# masterboard.net
KiCad netlist of a schematic drawn in EAGLE
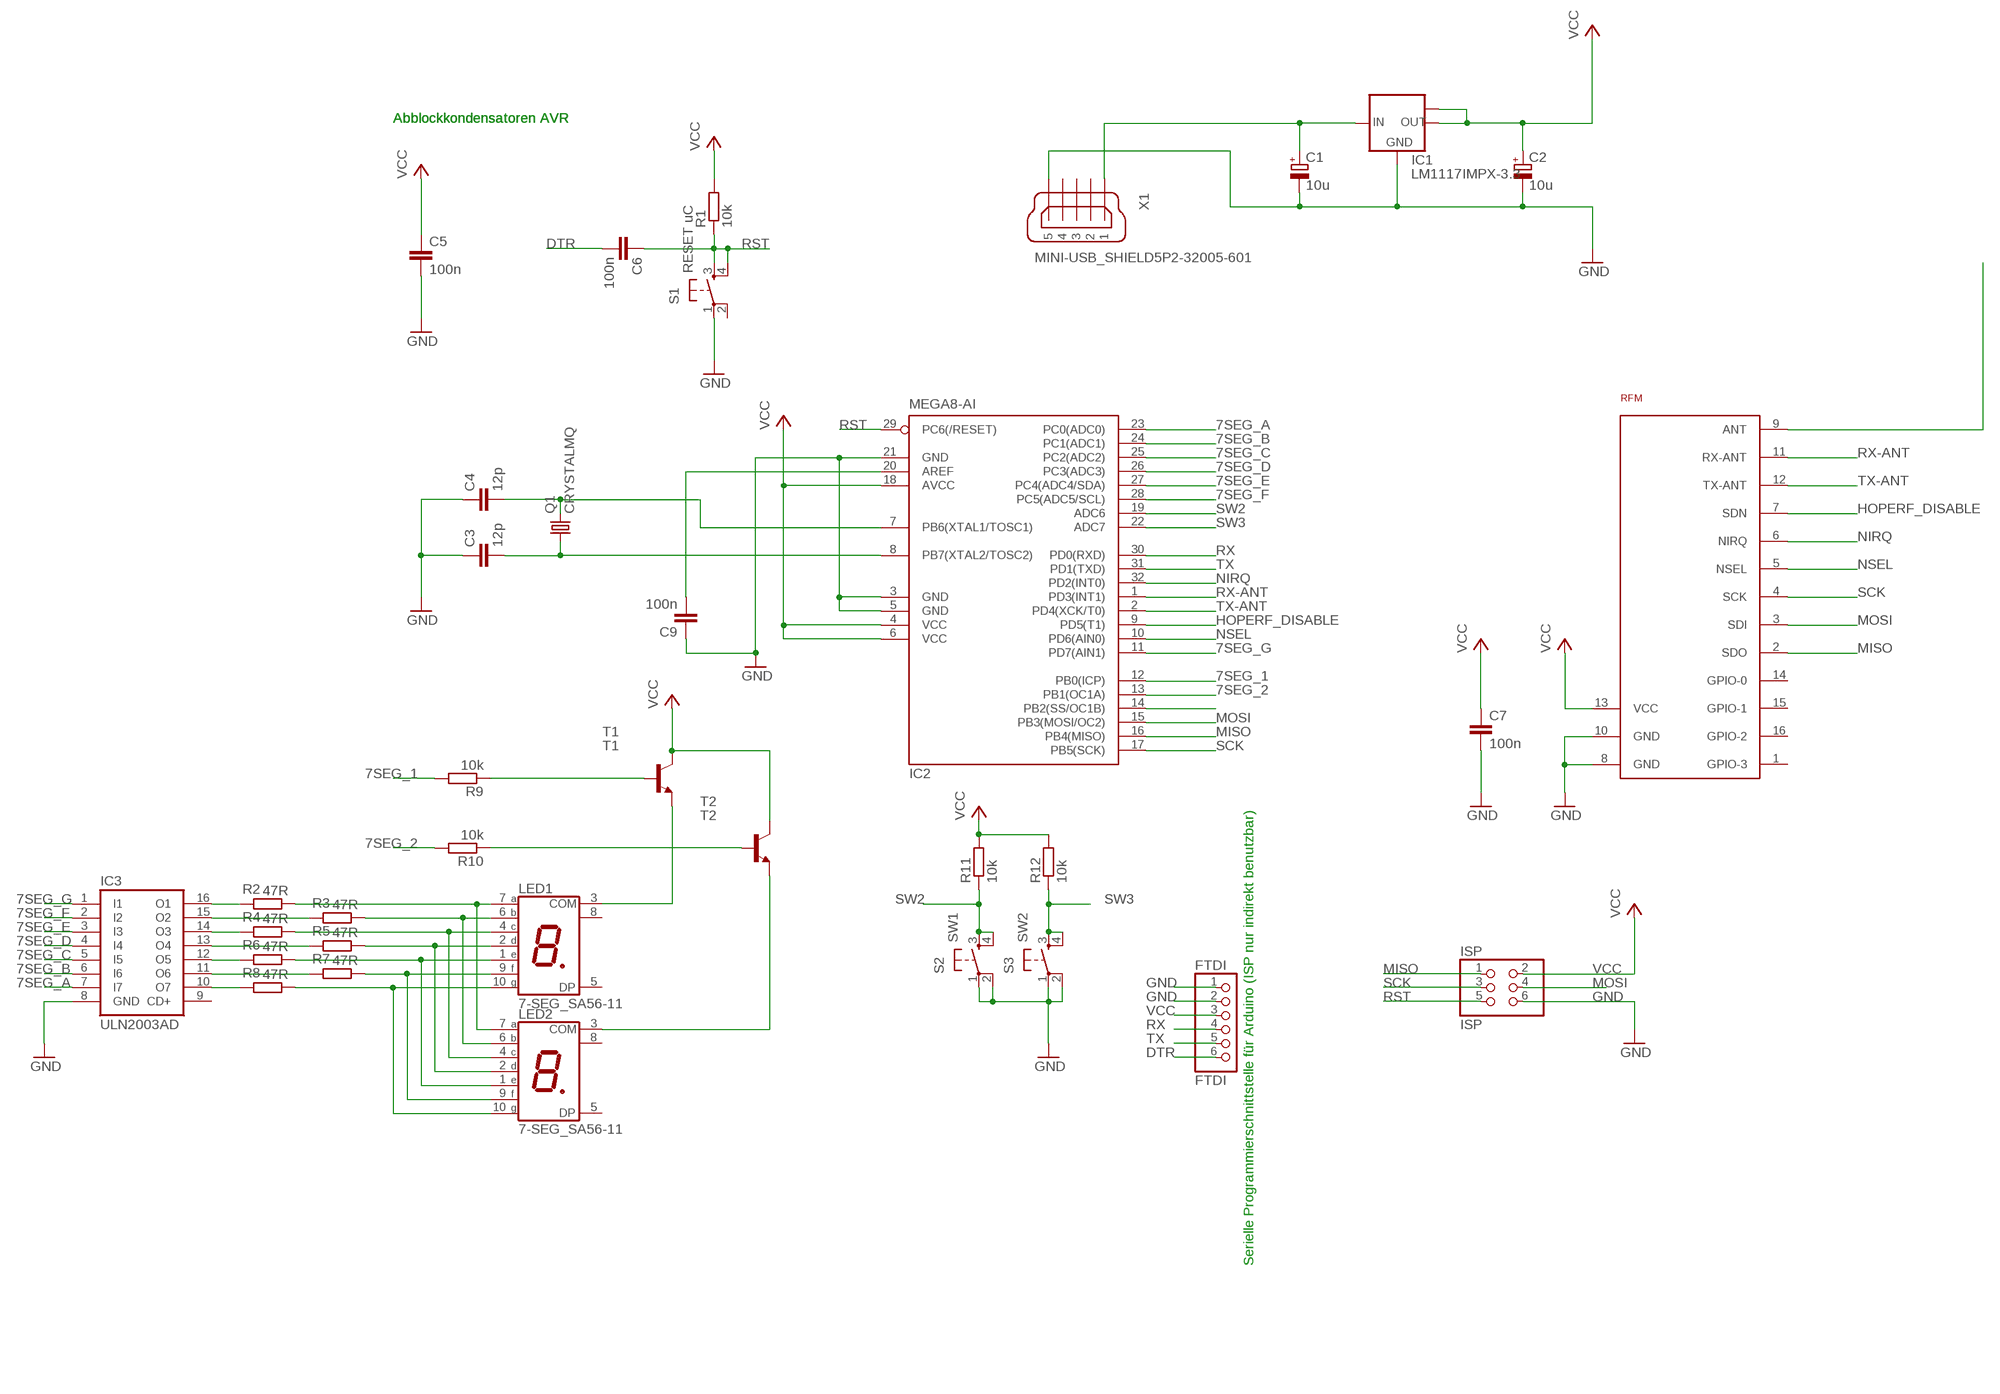
[diagram p0: schematic, sheet 1]

(export (version "E")
  (design (tool "Eeschema 10.0.6"))
  (components
    (comp (ref "C1")
      (value "10u")
      (footprint "eagle-import:CT6032")
      (libsource (lib "eagle-import") (part "CPOL-EUCT6032"))
    )
    (comp (ref "C2")
      (value "10u")
      (footprint "eagle-import:CT6032")
      (libsource (lib "eagle-import") (part "CPOL-EUCT6032"))
    )
    (comp (ref "C3")
      (value "12p")
      (footprint "eagle-import:C0603")
      (libsource (lib "eagle-import") (part "C-EUC0603"))
    )
    (comp (ref "C4")
      (value "12p")
      (footprint "eagle-import:C0603")
      (libsource (lib "eagle-import") (part "C-EUC0603"))
    )
    (comp (ref "C5")
      (value "100n")
      (footprint "eagle-import:C0603")
      (libsource (lib "eagle-import") (part "C-EUC0603"))
    )
    (comp (ref "C6")
      (value "100n")
      (footprint "eagle-import:C0603")
      (libsource (lib "eagle-import") (part "C-EUC0603"))
    )
    (comp (ref "C7")
      (value "100n")
      (footprint "eagle-import:C0603")
      (libsource (lib "eagle-import") (part "C-EUC0603"))
    )
    (comp (ref "C9")
      (value "100n")
      (footprint "eagle-import:C0603")
      (libsource (lib "eagle-import") (part "C-EUC0603"))
    )
    (comp (ref "FTDI")
      (value "FTDI")
      (footprint "eagle-import:1X06_90")
      (libsource (lib "eagle-import") (part "PINHD-1X6/90"))
    )
    (comp (ref "IC1")
      (value "LM1117IMPX-3.3")
      (footprint "eagle-import:SOT223")
      (libsource (lib "eagle-import") (part "LM1117IMPX-3.3"))
    )
    (comp (ref "IC2")
      (value "MEGA8-AI")
      (footprint "eagle-import:TQFP32-08")
      (fields (field (name "MPN") "ATMEGA8-16AU"))
      (libsource (lib "eagle-import") (part "MEGA8-AI"))
    )
    (comp (ref "IC3")
      (value "ULN2003AD")
      (footprint "eagle-import:SO16")
      (libsource (lib "eagle-import") (part "ULN2003AD"))
    )
    (comp (ref "ISP")
      (value "ISP")
      (footprint "eagle-import:2X03")
      (libsource (lib "eagle-import") (part "PINHD-2X3"))
    )
    (comp (ref "LED1")
      (value "7-SEG_SA56-11")
      (footprint "eagle-import:SA56-11")
      (libsource (lib "eagle-import") (part "7-SEG_SA56-11"))
    )
    (comp (ref "LED2")
      (value "7-SEG_SA56-11")
      (footprint "eagle-import:SA56-11")
      (libsource (lib "eagle-import") (part "7-SEG_SA56-11"))
    )
    (comp (ref "Q1")
      (value "CRYSTALMQ")
      (footprint "eagle-import:MQ")
      (libsource (lib "eagle-import") (part "CRYSTALMQ"))
    )
    (comp (ref "R1")
      (value "10k")
      (footprint "eagle-import:R0805")
      (libsource (lib "eagle-import") (part "R-EU_R0805"))
    )
    (comp (ref "R2")
      (value "47R")
      (footprint "eagle-import:R0805")
      (libsource (lib "eagle-import") (part "R-EU_R0805"))
    )
    (comp (ref "R3")
      (value "47R")
      (footprint "eagle-import:R0805")
      (libsource (lib "eagle-import") (part "R-EU_R0805"))
    )
    (comp (ref "R4")
      (value "47R")
      (footprint "eagle-import:R0805")
      (libsource (lib "eagle-import") (part "R-EU_R0805"))
    )
    (comp (ref "R5")
      (value "47R")
      (footprint "eagle-import:R0805")
      (libsource (lib "eagle-import") (part "R-EU_R0805"))
    )
    (comp (ref "R6")
      (value "47R")
      (footprint "eagle-import:R0805")
      (libsource (lib "eagle-import") (part "R-EU_R0805"))
    )
    (comp (ref "R7")
      (value "47R")
      (footprint "eagle-import:R0805")
      (libsource (lib "eagle-import") (part "R-EU_R0805"))
    )
    (comp (ref "R8")
      (value "47R")
      (footprint "eagle-import:R0805")
      (libsource (lib "eagle-import") (part "R-EU_R0805"))
    )
    (comp (ref "R9")
      (value "10k")
      (footprint "eagle-import:R0805")
      (libsource (lib "eagle-import") (part "R-EU_R0805"))
    )
    (comp (ref "R10")
      (value "10k")
      (footprint "eagle-import:R0805")
      (libsource (lib "eagle-import") (part "R-EU_R0805"))
    )
    (comp (ref "R11")
      (value "10k")
      (footprint "eagle-import:R0805")
      (libsource (lib "eagle-import") (part "R-EU_R0805"))
    )
    (comp (ref "R12")
      (value "10k")
      (footprint "eagle-import:R0805")
      (libsource (lib "eagle-import") (part "R-EU_R0805"))
    )
    (comp (ref "RFM")
      (value "HOPERF-DB")
      (footprint "eagle-import:HOPERF-DB")
      (libsource (lib "eagle-import") (part "HOPERF-DB"))
    )
    (comp (ref "S1")
      (value "RESET uC")
      (footprint "eagle-import:RAFI")
      (libsource (lib "eagle-import") (part "10-XXB3FRAFI"))
    )
    (comp (ref "S2")
      (value "SW1")
      (footprint "eagle-import:RAFI")
      (libsource (lib "eagle-import") (part "10-XXB3FRAFI"))
    )
    (comp (ref "S3")
      (value "SW2")
      (footprint "eagle-import:RAFI")
      (libsource (lib "eagle-import") (part "10-XXB3FRAFI"))
    )
    (comp (ref "T1")
      (value "T1")
      (footprint "eagle-import:SOT89-BCE")
      (libsource (lib "eagle-import") (part "-NPN-SOT89-BCEBCX54"))
    )
    (comp (ref "T2")
      (value "T2")
      (footprint "eagle-import:SOT89-BCE")
      (libsource (lib "eagle-import") (part "-NPN-SOT89-BCEBCX54"))
    )
    (comp (ref "X1")
      (value "MINI-USB_SHIELD5P2-32005-601")
      (footprint "eagle-import:32005-601")
      (libsource (lib "eagle-import") (part "MINI-USB_SHIELD5P2-32005-601"))
    )
  )
  (nets
    (net (code "1") (name "/7SEG_1") (class "Default")
      (node (ref "IC2") (pin "12") (pinfunction "PB0(ICP)_12") (pintype "bidirectional"))
      (node (ref "R9") (pin "2") (pinfunction "2_2") (pintype "passive"))
    )
    (net (code "2") (name "/7SEG_2") (class "Default")
      (node (ref "IC2") (pin "13") (pinfunction "PB1(OC1A)_13") (pintype "bidirectional"))
      (node (ref "R10") (pin "2") (pinfunction "2_2") (pintype "passive"))
    )
    (net (code "3") (name "/7SEG_A") (class "Default")
      (node (ref "IC2") (pin "23") (pinfunction "PC0(ADC0)_23") (pintype "bidirectional"))
      (node (ref "IC3") (pin "7") (pinfunction "I7_7") (pintype "input"))
    )
    (net (code "4") (name "/7SEG_B") (class "Default")
      (node (ref "IC2") (pin "24") (pinfunction "PC1(ADC1)_24") (pintype "bidirectional"))
      (node (ref "IC3") (pin "6") (pinfunction "I6_6") (pintype "input"))
    )
    (net (code "5") (name "/7SEG_C") (class "Default")
      (node (ref "IC2") (pin "25") (pinfunction "PC2(ADC2)_25") (pintype "bidirectional"))
      (node (ref "IC3") (pin "5") (pinfunction "I5_5") (pintype "input"))
    )
    (net (code "6") (name "/7SEG_D") (class "Default")
      (node (ref "IC2") (pin "26") (pinfunction "PC3(ADC3)_26") (pintype "bidirectional"))
      (node (ref "IC3") (pin "4") (pinfunction "I4_4") (pintype "input"))
    )
    (net (code "7") (name "/7SEG_E") (class "Default")
      (node (ref "IC2") (pin "27") (pinfunction "PC4(ADC4/SDA)_27") (pintype "bidirectional"))
      (node (ref "IC3") (pin "3") (pinfunction "I3_3") (pintype "input"))
    )
    (net (code "8") (name "/7SEG_F") (class "Default")
      (node (ref "IC2") (pin "28") (pinfunction "PC5(ADC5/SCL)_28") (pintype "bidirectional"))
      (node (ref "IC3") (pin "2") (pinfunction "I2_2") (pintype "input"))
    )
    (net (code "9") (name "/7SEG_G") (class "Default")
      (node (ref "IC2") (pin "11") (pinfunction "PD7(AIN1)_11") (pintype "bidirectional"))
      (node (ref "IC3") (pin "1") (pinfunction "I1_1") (pintype "input"))
    )
    (net (code "10") (name "/DTR") (class "Default")
      (node (ref "C6") (pin "2") (pinfunction "2_2") (pintype "passive"))
      (node (ref "FTDI") (pin "6") (pinfunction "6_6") (pintype "passive"))
    )
    (net (code "11") (name "/HOPERF_DISABLE") (class "Default")
      (node (ref "IC2") (pin "9") (pinfunction "PD5(T1)_9") (pintype "bidirectional"))
      (node (ref "RFM") (pin "7") (pinfunction "SDN_7") (pintype "bidirectional"))
    )
    (net (code "12") (name "/MISO") (class "Default")
      (node (ref "IC2") (pin "16") (pinfunction "PB4(MISO)_16") (pintype "bidirectional"))
      (node (ref "ISP") (pin "1") (pinfunction "1_1") (pintype "passive"))
      (node (ref "RFM") (pin "2") (pinfunction "SDO_2") (pintype "bidirectional"))
    )
    (net (code "13") (name "/MOSI") (class "Default")
      (node (ref "IC2") (pin "15") (pinfunction "PB3(MOSI/OC2)_15") (pintype "bidirectional"))
      (node (ref "ISP") (pin "4") (pinfunction "4_4") (pintype "passive"))
      (node (ref "RFM") (pin "3") (pinfunction "SDI_3") (pintype "bidirectional"))
    )
    (net (code "14") (name "/NIRQ") (class "Default")
      (node (ref "IC2") (pin "32") (pinfunction "PD2(INT0)_32") (pintype "bidirectional"))
      (node (ref "RFM") (pin "6") (pinfunction "NIRQ_6") (pintype "bidirectional"))
    )
    (net (code "15") (name "/NSEL") (class "Default")
      (node (ref "IC2") (pin "10") (pinfunction "PD6(AIN0)_10") (pintype "bidirectional"))
      (node (ref "RFM") (pin "5") (pinfunction "NSEL_5") (pintype "bidirectional"))
    )
    (net (code "16") (name "/RST") (class "Default")
      (node (ref "C6") (pin "1") (pinfunction "1_1") (pintype "passive"))
      (node (ref "IC2") (pin "29") (pinfunction "PC6(/RESET)_29") (pintype "bidirectional"))
      (node (ref "ISP") (pin "5") (pinfunction "5_5") (pintype "passive"))
      (node (ref "R1") (pin "1") (pinfunction "1_1") (pintype "passive"))
      (node (ref "S1") (pin "3") (pinfunction "S_3") (pintype "passive"))
      (node (ref "S1") (pin "4") (pinfunction "S1_4") (pintype "passive"))
    )
    (net (code "17") (name "/RX") (class "Default")
      (node (ref "FTDI") (pin "4") (pinfunction "4_4") (pintype "passive"))
      (node (ref "IC2") (pin "30") (pinfunction "PD0(RXD)_30") (pintype "bidirectional"))
    )
    (net (code "18") (name "/RX-ANT") (class "Default")
      (node (ref "IC2") (pin "1") (pinfunction "PD3(INT1)_1") (pintype "bidirectional"))
      (node (ref "RFM") (pin "11") (pinfunction "RX-ANT_11") (pintype "bidirectional"))
    )
    (net (code "19") (name "/SCK") (class "Default")
      (node (ref "IC2") (pin "17") (pinfunction "PB5(SCK)_17") (pintype "bidirectional"))
      (node (ref "ISP") (pin "3") (pinfunction "3_3") (pintype "passive"))
      (node (ref "RFM") (pin "4") (pinfunction "SCK_4") (pintype "bidirectional"))
    )
    (net (code "20") (name "/SW2") (class "Default")
      (node (ref "IC2") (pin "19") (pinfunction "ADC6_19") (pintype "bidirectional"))
      (node (ref "R11") (pin "1") (pinfunction "1_1") (pintype "passive"))
      (node (ref "S2") (pin "3") (pinfunction "S_3") (pintype "passive"))
      (node (ref "S2") (pin "4") (pinfunction "S1_4") (pintype "passive"))
    )
    (net (code "21") (name "/SW3") (class "Default")
      (node (ref "IC2") (pin "22") (pinfunction "ADC7_22") (pintype "bidirectional"))
      (node (ref "R12") (pin "1") (pinfunction "1_1") (pintype "passive"))
      (node (ref "S3") (pin "3") (pinfunction "S_3") (pintype "passive"))
      (node (ref "S3") (pin "4") (pinfunction "S1_4") (pintype "passive"))
    )
    (net (code "22") (name "/TX") (class "Default")
      (node (ref "FTDI") (pin "5") (pinfunction "5_5") (pintype "passive"))
      (node (ref "IC2") (pin "31") (pinfunction "PD1(TXD)_31") (pintype "bidirectional"))
    )
    (net (code "23") (name "/TX-ANT") (class "Default")
      (node (ref "IC2") (pin "2") (pinfunction "PD4(XCK/T0)_2") (pintype "bidirectional"))
      (node (ref "RFM") (pin "12") (pinfunction "TX-ANT_12") (pintype "bidirectional"))
    )
    (net (code "24") (name "GND") (class "Default")
      (node (ref "C1") (pin "-") (pinfunction "-_-") (pintype "passive"))
      (node (ref "C2") (pin "-") (pinfunction "-_-") (pintype "passive"))
      (node (ref "C3") (pin "1") (pinfunction "1_1") (pintype "passive"))
      (node (ref "C4") (pin "1") (pinfunction "1_1") (pintype "passive"))
      (node (ref "C5") (pin "2") (pinfunction "2_2") (pintype "passive"))
      (node (ref "C7") (pin "2") (pinfunction "2_2") (pintype "passive"))
      (node (ref "C9") (pin "1") (pinfunction "1_1") (pintype "passive"))
      (node (ref "FTDI") (pin "1") (pinfunction "1_1") (pintype "passive"))
      (node (ref "FTDI") (pin "2") (pinfunction "2_2") (pintype "passive"))
      (node (ref "IC1") (pin "1") (pinfunction "GND_1") (pintype "input"))
      (node (ref "IC2") (pin "21") (pinfunction "GND_21") (pintype "power_in"))
      (node (ref "IC2") (pin "3") (pinfunction "GND_3") (pintype "power_in"))
      (node (ref "IC2") (pin "5") (pinfunction "GND_5") (pintype "power_in"))
      (node (ref "IC3") (pin "8") (pinfunction "GND_8") (pintype "power_in"))
      (node (ref "ISP") (pin "6") (pinfunction "6_6") (pintype "passive"))
      (node (ref "RFM") (pin "10") (pinfunction "GND_10") (pintype "bidirectional"))
      (node (ref "RFM") (pin "8") (pinfunction "GND_8") (pintype "bidirectional"))
      (node (ref "S1") (pin "1") (pinfunction "P_1") (pintype "passive"))
      (node (ref "S2") (pin "1") (pinfunction "P_1") (pintype "passive"))
      (node (ref "S2") (pin "2") (pinfunction "P1_2") (pintype "passive"))
      (node (ref "S3") (pin "1") (pinfunction "P_1") (pintype "passive"))
      (node (ref "S3") (pin "2") (pinfunction "P1_2") (pintype "passive"))
      (node (ref "X1") (pin "5") (pinfunction "5_5") (pintype "passive"))
    )
    (net (code "25") (name "Net-(IC1-IN)") (class "Default")
      (node (ref "C1") (pin "+") (pinfunction "+_+") (pintype "passive"))
      (node (ref "IC1") (pin "3") (pinfunction "IN_3") (pintype "input"))
      (node (ref "X1") (pin "1") (pinfunction "1_1") (pintype "passive"))
    )
    (net (code "26") (name "Net-(IC2-AREF)") (class "Default")
      (node (ref "C9") (pin "2") (pinfunction "2_2") (pintype "passive"))
      (node (ref "IC2") (pin "20") (pinfunction "AREF_20") (pintype "passive"))
    )
    (net (code "27") (name "Net-(IC2-PB6(XTAL1{slash}TOSC1))") (class "Default")
      (node (ref "C4") (pin "2") (pinfunction "2_2") (pintype "passive"))
      (node (ref "IC2") (pin "7") (pinfunction "PB6(XTAL1/TOSC1)_7") (pintype "bidirectional"))
      (node (ref "Q1") (pin "P3") (pinfunction "2_P3") (pintype "passive"))
    )
    (net (code "28") (name "Net-(IC2-PB7(XTAL2{slash}TOSC2))") (class "Default")
      (node (ref "C3") (pin "2") (pinfunction "2_2") (pintype "passive"))
      (node (ref "IC2") (pin "8") (pinfunction "PB7(XTAL2/TOSC2)_8") (pintype "bidirectional"))
      (node (ref "Q1") (pin "P1") (pinfunction "1_P1") (pintype "passive"))
    )
    (net (code "29") (name "Net-(IC3-O1)") (class "Default")
      (node (ref "IC3") (pin "16") (pinfunction "O1_16") (pintype "open_collector"))
      (node (ref "R2") (pin "2") (pinfunction "2_2") (pintype "passive"))
    )
    (net (code "30") (name "Net-(IC3-O2)") (class "Default")
      (node (ref "IC3") (pin "15") (pinfunction "O2_15") (pintype "open_collector"))
      (node (ref "R3") (pin "2") (pinfunction "2_2") (pintype "passive"))
    )
    (net (code "31") (name "Net-(IC3-O3)") (class "Default")
      (node (ref "IC3") (pin "14") (pinfunction "O3_14") (pintype "open_collector"))
      (node (ref "R4") (pin "2") (pinfunction "2_2") (pintype "passive"))
    )
    (net (code "32") (name "Net-(IC3-O4)") (class "Default")
      (node (ref "IC3") (pin "13") (pinfunction "O4_13") (pintype "open_collector"))
      (node (ref "R5") (pin "2") (pinfunction "2_2") (pintype "passive"))
    )
    (net (code "33") (name "Net-(IC3-O5)") (class "Default")
      (node (ref "IC3") (pin "12") (pinfunction "O5_12") (pintype "open_collector"))
      (node (ref "R6") (pin "2") (pinfunction "2_2") (pintype "passive"))
    )
    (net (code "34") (name "Net-(IC3-O6)") (class "Default")
      (node (ref "IC3") (pin "11") (pinfunction "O6_11") (pintype "open_collector"))
      (node (ref "R7") (pin "2") (pinfunction "2_2") (pintype "passive"))
    )
    (net (code "35") (name "Net-(IC3-O7)") (class "Default")
      (node (ref "IC3") (pin "10") (pinfunction "O7_10") (pintype "open_collector"))
      (node (ref "R8") (pin "2") (pinfunction "2_2") (pintype "passive"))
    )
    (net (code "36") (name "Net-(LED1-A)") (class "Default")
      (node (ref "LED1") (pin "7") (pinfunction "A_7") (pintype "passive"))
      (node (ref "LED2") (pin "7") (pinfunction "A_7") (pintype "passive"))
      (node (ref "R2") (pin "1") (pinfunction "1_1") (pintype "passive"))
    )
    (net (code "37") (name "Net-(LED1-B)") (class "Default")
      (node (ref "LED1") (pin "6") (pinfunction "B_6") (pintype "passive"))
      (node (ref "LED2") (pin "6") (pinfunction "B_6") (pintype "passive"))
      (node (ref "R3") (pin "1") (pinfunction "1_1") (pintype "passive"))
    )
    (net (code "38") (name "Net-(LED1-C)") (class "Default")
      (node (ref "LED1") (pin "4") (pinfunction "C_4") (pintype "passive"))
      (node (ref "LED2") (pin "4") (pinfunction "C_4") (pintype "passive"))
      (node (ref "R4") (pin "1") (pinfunction "1_1") (pintype "passive"))
    )
    (net (code "39") (name "Net-(LED1-COM-Pad3)") (class "Default")
      (node (ref "LED1") (pin "3") (pinfunction "COM_3") (pintype "passive"))
      (node (ref "T1") (pin "E") (pinfunction "E_E") (pintype "passive"))
    )
    (net (code "40") (name "Net-(LED1-D)") (class "Default")
      (node (ref "LED1") (pin "2") (pinfunction "D_2") (pintype "passive"))
      (node (ref "LED2") (pin "2") (pinfunction "D_2") (pintype "passive"))
      (node (ref "R5") (pin "1") (pinfunction "1_1") (pintype "passive"))
    )
    (net (code "41") (name "Net-(LED1-E)") (class "Default")
      (node (ref "LED1") (pin "1") (pinfunction "E_1") (pintype "passive"))
      (node (ref "LED2") (pin "1") (pinfunction "E_1") (pintype "passive"))
      (node (ref "R6") (pin "1") (pinfunction "1_1") (pintype "passive"))
    )
    (net (code "42") (name "Net-(LED1-F)") (class "Default")
      (node (ref "LED1") (pin "9") (pinfunction "F_9") (pintype "passive"))
      (node (ref "LED2") (pin "9") (pinfunction "F_9") (pintype "passive"))
      (node (ref "R7") (pin "1") (pinfunction "1_1") (pintype "passive"))
    )
    (net (code "43") (name "Net-(LED1-G)") (class "Default")
      (node (ref "LED1") (pin "10") (pinfunction "G_10") (pintype "passive"))
      (node (ref "LED2") (pin "10") (pinfunction "G_10") (pintype "passive"))
      (node (ref "R8") (pin "1") (pinfunction "1_1") (pintype "passive"))
    )
    (net (code "44") (name "Net-(LED2-COM-Pad3)") (class "Default")
      (node (ref "LED2") (pin "3") (pinfunction "COM_3") (pintype "passive"))
      (node (ref "T2") (pin "E") (pinfunction "E_E") (pintype "passive"))
    )
    (net (code "45") (name "Net-(R9-Pad1)") (class "Default")
      (node (ref "R9") (pin "1") (pinfunction "1_1") (pintype "passive"))
      (node (ref "T1") (pin "B") (pinfunction "B_B") (pintype "passive"))
    )
    (net (code "46") (name "Net-(R10-Pad1)") (class "Default")
      (node (ref "R10") (pin "1") (pinfunction "1_1") (pintype "passive"))
      (node (ref "T2") (pin "B") (pinfunction "B_B") (pintype "passive"))
    )
    (net (code "47") (name "VCC") (class "Default")
      (node (ref "C2") (pin "+") (pinfunction "+_+") (pintype "passive"))
      (node (ref "C5") (pin "1") (pinfunction "1_1") (pintype "passive"))
      (node (ref "C7") (pin "1") (pinfunction "1_1") (pintype "passive"))
      (node (ref "FTDI") (pin "3") (pinfunction "3_3") (pintype "passive"))
      (node (ref "IC1") (pin "2") (pinfunction "OUT_2") (pintype "passive"))
      (node (ref "IC1") (pin "TAB") (pinfunction "OUT1_TAB") (pintype "passive"))
      (node (ref "IC2") (pin "18") (pinfunction "AVCC_18") (pintype "power_in"))
      (node (ref "IC2") (pin "4") (pinfunction "VCC_4") (pintype "power_in"))
      (node (ref "IC2") (pin "6") (pinfunction "VCC_6") (pintype "power_in"))
      (node (ref "ISP") (pin "2") (pinfunction "2_2") (pintype "passive"))
      (node (ref "R1") (pin "2") (pinfunction "2_2") (pintype "passive"))
      (node (ref "R11") (pin "2") (pinfunction "2_2") (pintype "passive"))
      (node (ref "R12") (pin "2") (pinfunction "2_2") (pintype "passive"))
      (node (ref "RFM") (pin "13") (pinfunction "VCC_13") (pintype "bidirectional"))
      (node (ref "T1") (pin "C") (pinfunction "C_C") (pintype "passive"))
      (node (ref "T2") (pin "C") (pinfunction "C_C") (pintype "passive"))
    )
    (net (code "48") (name "unconnected-(IC2-PB2(SS{slash}OC1B)-Pad14)") (class "Default")
      (node (ref "IC2") (pin "14") (pinfunction "PB2(SS/OC1B)_14") (pintype "bidirectional"))
    )
    (net (code "49") (name "unconnected-(IC3-CD+-Pad9)") (class "Default")
      (node (ref "IC3") (pin "9") (pinfunction "CD+_9") (pintype "passive"))
    )
    (net (code "50") (name "unconnected-(LED1-COM-Pad8)") (class "Default")
      (node (ref "LED1") (pin "8") (pinfunction "COM_8") (pintype "passive"))
    )
    (net (code "51") (name "unconnected-(LED1-DP-Pad5)") (class "Default")
      (node (ref "LED1") (pin "5") (pinfunction "DP_5") (pintype "passive"))
    )
    (net (code "52") (name "unconnected-(LED2-COM-Pad8)") (class "Default")
      (node (ref "LED2") (pin "8") (pinfunction "COM_8") (pintype "passive"))
    )
    (net (code "53") (name "unconnected-(LED2-DP-Pad5)") (class "Default")
      (node (ref "LED2") (pin "5") (pinfunction "DP_5") (pintype "passive"))
    )
    (net (code "54") (name "unconnected-(RFM-ANT-Pad9)") (class "Default")
      (node (ref "RFM") (pin "9") (pinfunction "ANT_9") (pintype "bidirectional"))
    )
    (net (code "55") (name "unconnected-(RFM-GPIO-0-Pad14)") (class "Default")
      (node (ref "RFM") (pin "14") (pinfunction "GPIO-0_14") (pintype "bidirectional"))
    )
    (net (code "56") (name "unconnected-(RFM-GPIO-1-Pad15)") (class "Default")
      (node (ref "RFM") (pin "15") (pinfunction "GPIO-1_15") (pintype "bidirectional"))
    )
    (net (code "57") (name "unconnected-(RFM-GPIO-2-Pad16)") (class "Default")
      (node (ref "RFM") (pin "16") (pinfunction "GPIO-2_16") (pintype "bidirectional"))
    )
    (net (code "58") (name "unconnected-(RFM-GPIO-3-Pad1)") (class "Default")
      (node (ref "RFM") (pin "1") (pinfunction "GPIO-3_1") (pintype "bidirectional"))
    )
    (net (code "59") (name "unconnected-(S1-P1-Pad2)") (class "Default")
      (node (ref "S1") (pin "2") (pinfunction "P1_2") (pintype "passive"))
    )
    (net (code "60") (name "unconnected-(X1-Pad2)") (class "Default")
      (node (ref "X1") (pin "2") (pinfunction "2_2") (pintype "passive"))
    )
    (net (code "61") (name "unconnected-(X1-Pad3)") (class "Default")
      (node (ref "X1") (pin "3") (pinfunction "3_3") (pintype "passive"))
    )
    (net (code "62") (name "unconnected-(X1-Pad4)") (class "Default")
      (node (ref "X1") (pin "4") (pinfunction "4_4") (pintype "passive"))
    )
  )
)
